# 3V3_MCU.net
KiCad netlist of a schematic drawn in Altium Designer
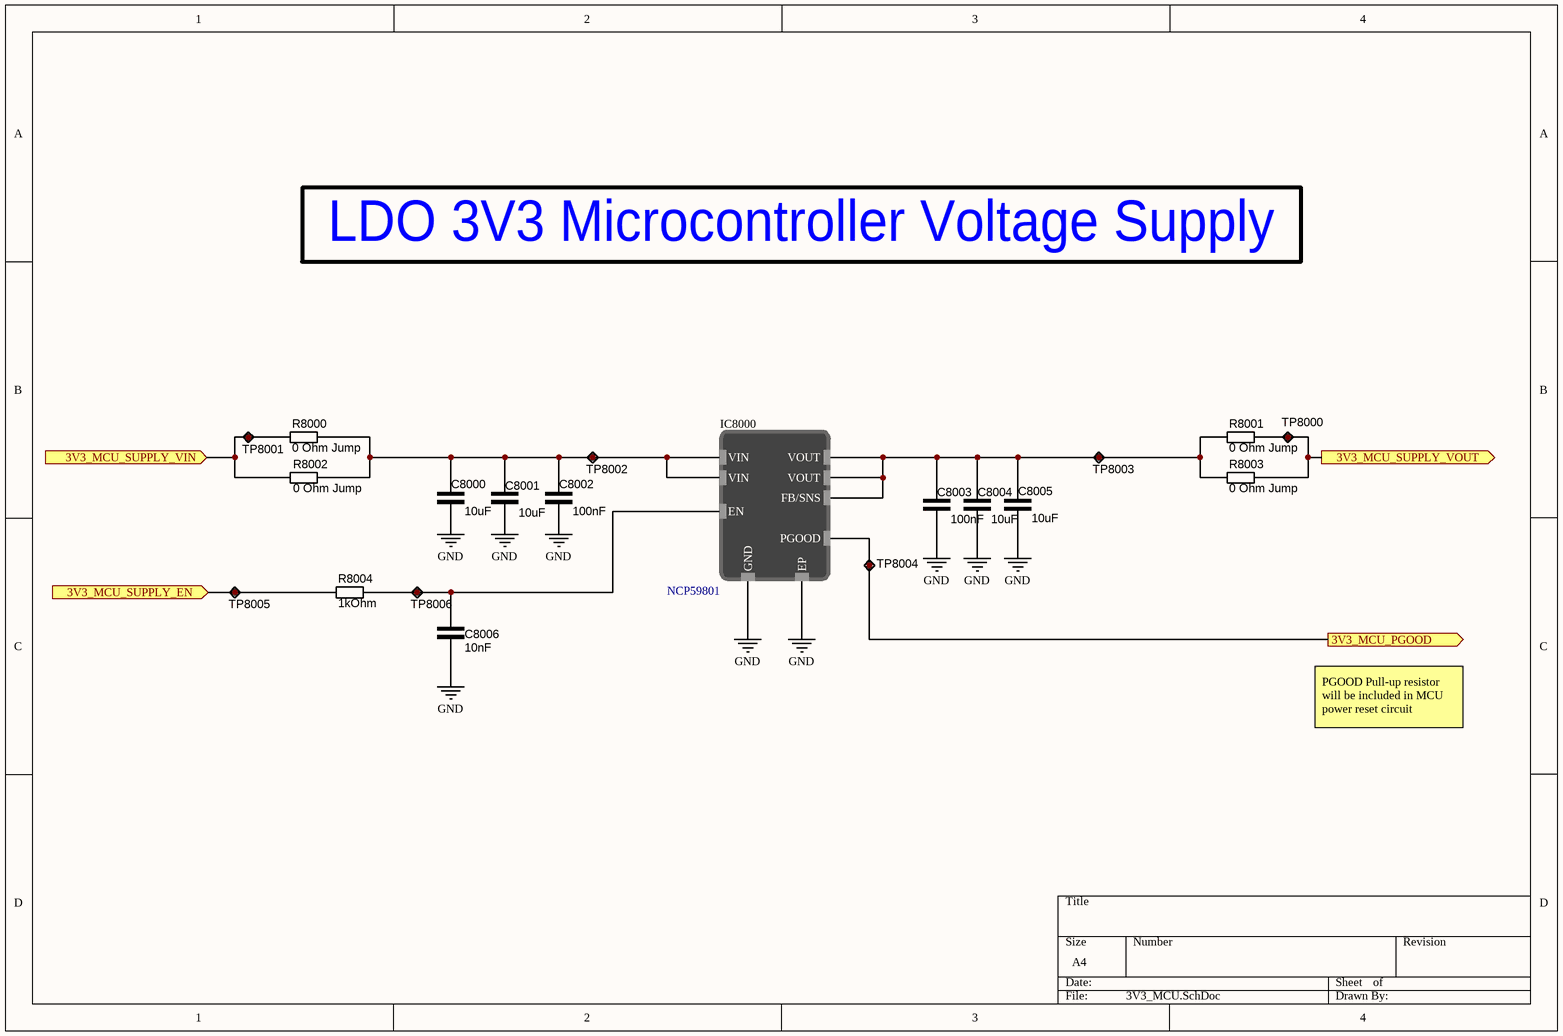
[diagram p0: 3V3_MCU.SchDoc]

(export (version "E")
  (design (tool "Eeschema 10.0.6"))
  (components
    (comp (ref "C8000")
      (value "10uF")
      (footprint "CAP_0805")
      (description "10 µF ±10% 25V Ceramic Capacitor X5R 0805 (2012 Metric)")
      (fields (field (name "DIGIKEY PART NUMBER") "445-5984-1-ND"))
      (libsource (lib "CapacitorsIntegrated") (part "C000002"))
    )
    (comp (ref "C8001")
      (value "10uF")
      (footprint "CAP_0805")
      (description "10 µF ±10% 25V Ceramic Capacitor X5R 0805 (2012 Metric)")
      (fields (field (name "DIGIKEY PART NUMBER") "445-5984-1-ND"))
      (libsource (lib "") (part "C000002_1"))
    )
    (comp (ref "C8002")
      (value "100nF")
      (footprint "CAP_0603")
      (description "0.1 µF ±10% 25V Ceramic Capacitor X7R 0603 (1608 Metric)")
      (fields (field (name "DIGIKEY PART NUMBER") "478-KAM15AR71E104KTCT-ND"))
      (libsource (lib "") (part "C000007_1"))
    )
    (comp (ref "C8003")
      (value "100nF")
      (footprint "CAP_0603")
      (description "0.1 µF ±10% 25V Ceramic Capacitor X7R 0603 (1608 Metric)")
      (fields (field (name "DIGIKEY PART NUMBER") "478-KAM15AR71E104KTCT-ND"))
      (libsource (lib "CapacitorsIntegrated") (part "C000007"))
    )
    (comp (ref "C8004")
      (value "10uF")
      (footprint "CAP_0805")
      (description "10 µF ±10% 25V Ceramic Capacitor X5R 0805 (2012 Metric)")
      (fields (field (name "DIGIKEY PART NUMBER") "445-5984-1-ND"))
      (libsource (lib "") (part "C000002_1"))
    )
    (comp (ref "C8005")
      (value "10uF")
      (footprint "CAP_0805")
      (description "10 µF ±10% 25V Ceramic Capacitor X5R 0805 (2012 Metric)")
      (fields (field (name "DIGIKEY PART NUMBER") "445-5984-1-ND"))
      (libsource (lib "CapacitorsIntegrated") (part "C000002"))
    )
    (comp (ref "C8006")
      (value "10nF")
      (footprint "CAP_0603")
      (description "10000 pF ±20% 25V Ceramic Capacitor X7R 0603 (1608 Metric)")
      (fields (field (name "DIGIKEY PART NUMBER") "478-KGM15AR71E103MTCT-ND"))
      (libsource (lib "CapacitorsIntegrated") (part "C000005"))
    )
    (comp (ref "IC8000")
      (value "NCP59801")
      (footprint "DFNW8_3x3")
      (description "Linear Voltage Regulator IC Positive Fixed 1 Output 1A 8-DFNW (3x3)")
      (fields
        (field (name "DIGIKEY PART NUMBER") "488-NCP59801CML330TCGCT-ND")
        (field (name "MOUSER PART NUMBER") "863-CP59801CML330TCG")
      )
      (libsource (lib "IntegratedCircuits") (part "NCP59801"))
    )
    (comp (ref "R8000")
      (value "0 Ohm Jump")
      (footprint "RES_0603")
      (description "0 Ohms Jumper Chip Resistor 0603 (1608 Metric) Automotive AEC-Q200 Thick Film")
      (fields (field (name "DIGIKEY PART NUMBER") "RMCF0603ZT0R00CT-ND"))
      (libsource (lib "") (part "R000007_1"))
    )
    (comp (ref "R8001")
      (value "0 Ohm Jump")
      (footprint "RES_0805")
      (description "0 Ohms Jumper Chip Resistor 0805 (2012 Metric) Automotive AEC-Q200 Thick Film")
      (fields (field (name "DIGIKEY PART NUMBER") "P0.0ACT-ND"))
      (libsource (lib "ResistorsIntegrated") (part "R000011"))
    )
    (comp (ref "R8002")
      (value "0 Ohm Jump")
      (footprint "RES_0603")
      (description "0 Ohms Jumper Chip Resistor 0603 (1608 Metric) Automotive AEC-Q200 Thick Film")
      (fields (field (name "DIGIKEY PART NUMBER") "RMCF0603ZT0R00CT-ND"))
      (libsource (lib "ResistorsIntegrated") (part "R000007"))
    )
    (comp (ref "R8003")
      (value "0 Ohm Jump")
      (footprint "RES_0805")
      (description "0 Ohms Jumper Chip Resistor 0805 (2012 Metric) Automotive AEC-Q200 Thick Film")
      (fields (field (name "DIGIKEY PART NUMBER") "P0.0ACT-ND"))
      (libsource (lib "ResistorsIntegrated") (part "R000011"))
    )
    (comp (ref "R8004")
      (value "1kOhm")
      (footprint "RES_0603")
      (description "1 kOhms ±1% 0.125W, 1/8W Chip Resistor 0603 (1608 Metric) Anti-Sulfur Thin Film")
      (fields (field (name "DIGIKEY PART NUMBER") "MCT0603-1.00K-CFCT-ND"))
      (libsource (lib "ResistorsIntegrated") (part "R000004"))
    )
    (comp (ref "TP8000")
      (value "Test point")
      (footprint "TestPoint")
      (description "Test point 1mm")
      (libsource (lib "IntegratedCircuits") (part "TP002"))
    )
    (comp (ref "TP8001")
      (value "Test point")
      (footprint "TestPoint")
      (description "Test point 1mm")
      (libsource (lib "IntegratedCircuits") (part "TP002"))
    )
    (comp (ref "TP8002")
      (value "Test point")
      (footprint "TestPoint")
      (description "Test point 1mm")
      (libsource (lib "IntegratedCircuits") (part "TP002"))
    )
    (comp (ref "TP8003")
      (value "Test point")
      (footprint "TestPoint")
      (description "Test point 1mm")
      (libsource (lib "IntegratedCircuits") (part "TP002"))
    )
    (comp (ref "TP8004")
      (value "Test point")
      (footprint "TestPoint")
      (description "Test point 1mm")
      (libsource (lib "IntegratedCircuits") (part "TP002"))
    )
    (comp (ref "TP8005")
      (value "Test point")
      (footprint "TestPoint")
      (description "Test point 1mm")
      (libsource (lib "IntegratedCircuits") (part "TP002"))
    )
    (comp (ref "TP8006")
      (value "Test point")
      (footprint "TestPoint")
      (description "Test point 1mm")
      (libsource (lib "IntegratedCircuits") (part "TP002"))
    )
  )
  (nets
    (net (code "1") (name "/3V3_MCU_PGOOD") (class "Default")
      (node (ref "IC8000") (pin "6") (pinfunction "PGOOD_6") (pintype "passive"))
      (node (ref "TP8004") (pin "1") (pinfunction "1_1") (pintype "passive"))
    )
    (net (code "2") (name "/3V3_MCU_SUPPLY_EN") (class "Default")
      (node (ref "R8004") (pin "1") (pinfunction "1_1") (pintype "passive"))
      (node (ref "TP8005") (pin "1") (pinfunction "1_1") (pintype "passive"))
    )
    (net (code "3") (name "/3V3_MCU_SUPPLY_VIN") (class "Default")
      (node (ref "R8000") (pin "1") (pinfunction "1_1") (pintype "passive"))
      (node (ref "R8002") (pin "2") (pinfunction "2_2") (pintype "passive"))
      (node (ref "TP8001") (pin "1") (pinfunction "1_1") (pintype "passive"))
    )
    (net (code "4") (name "/3V3_MCU_SUPPLY_VOUT") (class "Default")
      (node (ref "R8001") (pin "2") (pinfunction "2_2") (pintype "passive"))
      (node (ref "R8003") (pin "2") (pinfunction "2_2") (pintype "passive"))
      (node (ref "TP8000") (pin "1") (pinfunction "1_1") (pintype "passive"))
    )
    (net (code "5") (name "GND") (class "Default")
      (node (ref "C8003") (pin "1") (pinfunction "1_1") (pintype "passive"))
      (node (ref "C8004") (pin "1") (pinfunction "1_1") (pintype "passive"))
      (node (ref "C8005") (pin "2") (pinfunction "2_2") (pintype "passive"))
      (node (ref "C8006") (pin "1") (pinfunction "1_1") (pintype "passive"))
      (node (ref "IC8000") (pin "4") (pinfunction "GND_4") (pintype "power_in"))
      (node (ref "IC8000") (pin "9") (pinfunction "EP_9") (pintype "passive"))
    )
    (net (code "6") (name "Net-(C8000-Pad1)") (class "Default")
      (node (ref "C8000") (pin "1") (pinfunction "1_1") (pintype "passive"))
      (node (ref "C8001") (pin "2") (pinfunction "2_2") (pintype "passive"))
      (node (ref "C8002") (pin "1") (pinfunction "1_1") (pintype "passive"))
      (node (ref "IC8000") (pin "7") (pinfunction "VIN_7") (pintype "passive"))
      (node (ref "IC8000") (pin "8") (pinfunction "VIN_8") (pintype "passive"))
      (node (ref "R8000") (pin "2") (pinfunction "2_2") (pintype "passive"))
      (node (ref "R8002") (pin "1") (pinfunction "1_1") (pintype "passive"))
      (node (ref "TP8002") (pin "1") (pinfunction "1_1") (pintype "passive"))
    )
    (net (code "7") (name "Net-(IC8000-EN)") (class "Default")
      (node (ref "C8006") (pin "2") (pinfunction "2_2") (pintype "passive"))
      (node (ref "IC8000") (pin "5") (pinfunction "EN_5") (pintype "passive"))
      (node (ref "R8004") (pin "2") (pinfunction "2_2") (pintype "passive"))
      (node (ref "TP8006") (pin "1") (pinfunction "1_1") (pintype "passive"))
    )
    (net (code "8") (name "Net-(IC8000-FB{slash}SNS)") (class "Default")
      (node (ref "C8003") (pin "2") (pinfunction "2_2") (pintype "passive"))
      (node (ref "C8004") (pin "2") (pinfunction "2_2") (pintype "passive"))
      (node (ref "C8005") (pin "1") (pinfunction "1_1") (pintype "passive"))
      (node (ref "IC8000") (pin "1") (pinfunction "VOUT_1") (pintype "open_collector"))
      (node (ref "IC8000") (pin "2") (pinfunction "VOUT_2") (pintype "passive"))
      (node (ref "IC8000") (pin "3") (pinfunction "FB/SNS_3") (pintype "passive"))
      (node (ref "R8001") (pin "1") (pinfunction "1_1") (pintype "passive"))
      (node (ref "R8003") (pin "1") (pinfunction "1_1") (pintype "passive"))
      (node (ref "TP8003") (pin "1") (pinfunction "1_1") (pintype "passive"))
    )
    (net (code "9") (name "unconnected-(C8000-Pad2)") (class "Default")
      (node (ref "C8000") (pin "2") (pinfunction "2_2") (pintype "passive"))
    )
    (net (code "10") (name "unconnected-(C8001-Pad1)") (class "Default")
      (node (ref "C8001") (pin "1") (pinfunction "1_1") (pintype "passive"))
    )
    (net (code "11") (name "unconnected-(C8002-Pad2)") (class "Default")
      (node (ref "C8002") (pin "2") (pinfunction "2_2") (pintype "passive"))
    )
  )
)
